# OpenBook_Schematic_v38.net
KiCad netlist of a schematic drawn in EAGLE
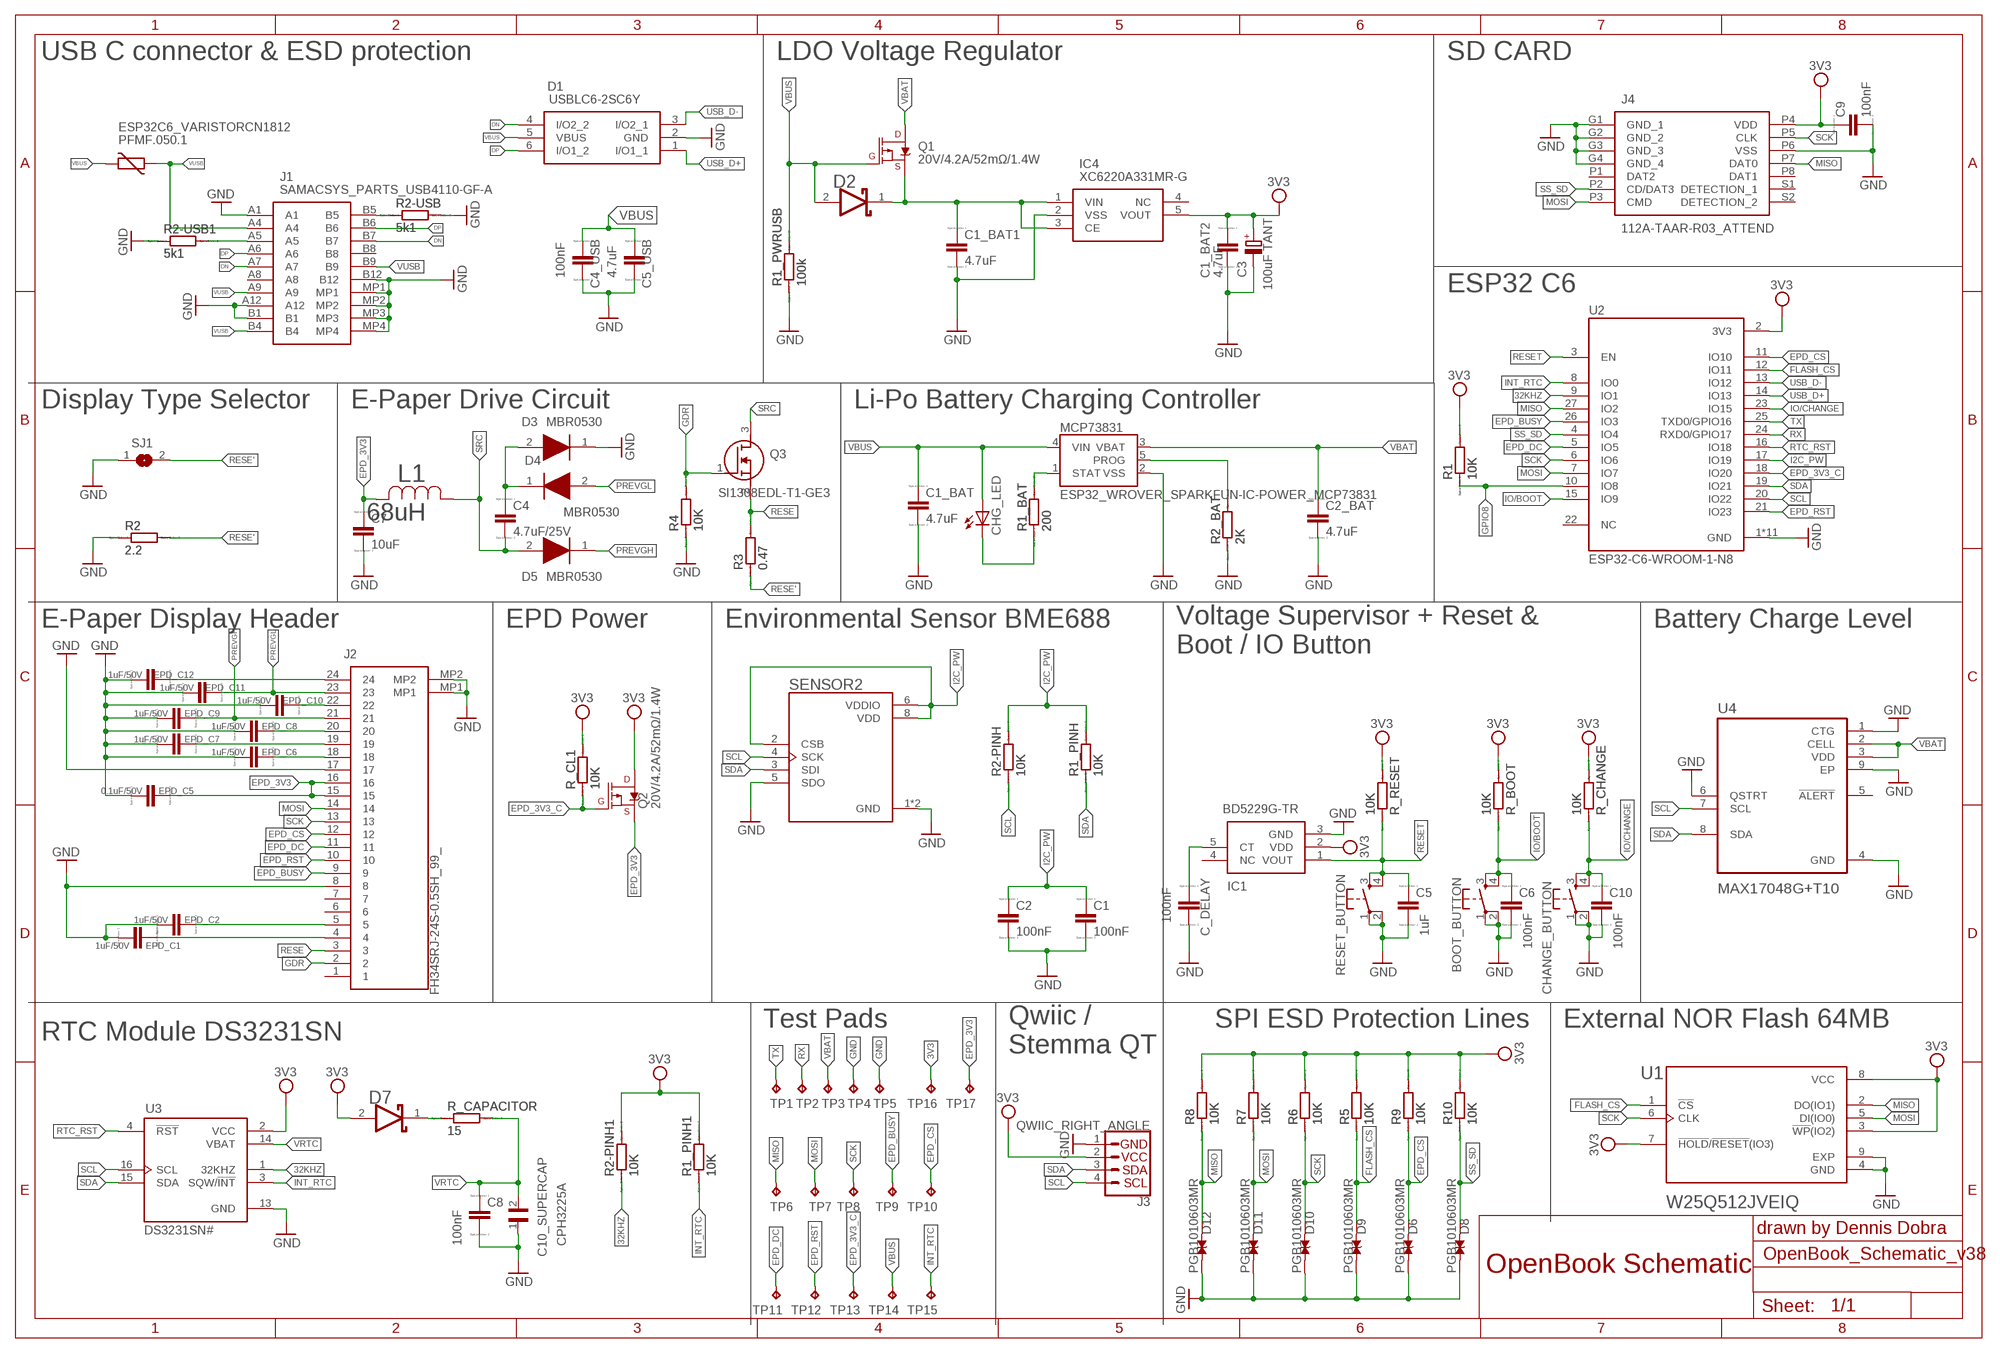
[diagram p0: schematic, sheet 1]

(export (version "E")
  (design (tool "Eeschema 10.0.6"))
  (components
    (comp (ref "BOOT_BUTTON")
      (value "BUTTON_CUSYOMV1")
      (footprint "eagle-import:MYBUTTON")
      (libsource (lib "eagle-import") (part "BUTTON_CUSYOMV1"))
    )
    (comp (ref "C1")
      (value "100nF")
      (footprint "eagle-import:EAGLE-LTSPICE_C0402")
      (libsource (lib "eagle-import") (part "EAGLE-LTSPICE_CC0402"))
    )
    (comp (ref "C1_BAT")
      (value "4.7uF")
      (footprint "eagle-import:EAGLE-LTSPICE_C0402")
      (libsource (lib "eagle-import") (part "EAGLE-LTSPICE_CC0402"))
    )
    (comp (ref "C1_BAT1")
      (value "4.7uF")
      (footprint "eagle-import:EAGLE-LTSPICE_C0402")
      (libsource (lib "eagle-import") (part "EAGLE-LTSPICE_CC0402"))
    )
    (comp (ref "C1_BAT2")
      (value "4.7uF")
      (footprint "eagle-import:EAGLE-LTSPICE_C0402")
      (libsource (lib "eagle-import") (part "EAGLE-LTSPICE_CC0402"))
    )
    (comp (ref "C2")
      (value "100nF")
      (footprint "eagle-import:EAGLE-LTSPICE_C0402")
      (libsource (lib "eagle-import") (part "EAGLE-LTSPICE_CC0402"))
    )
    (comp (ref "C2_BAT")
      (value "4.7uF")
      (footprint "eagle-import:EAGLE-LTSPICE_C0402")
      (libsource (lib "eagle-import") (part "EAGLE-LTSPICE_CC0402"))
    )
    (comp (ref "C3")
      (value "100uF TANT")
      (footprint "eagle-import:RCL_CT3528")
      (libsource (lib "eagle-import") (part "RCL_CPOL-EUCT3528"))
    )
    (comp (ref "C4")
      (value "4.7uF/25V")
      (footprint "eagle-import:EAGLE-LTSPICE_C0402")
      (libsource (lib "eagle-import") (part "EAGLE-LTSPICE_CC0402"))
    )
    (comp (ref "C4_USB")
      (value "100nF")
      (footprint "eagle-import:EAGLE-LTSPICE_C0402")
      (libsource (lib "eagle-import") (part "EAGLE-LTSPICE_CC0402"))
    )
    (comp (ref "C5")
      (value "1uF")
      (footprint "eagle-import:EAGLE-LTSPICE_C0402")
      (libsource (lib "eagle-import") (part "EAGLE-LTSPICE_CC0402"))
    )
    (comp (ref "C5_USB")
      (value "4.7uF")
      (footprint "eagle-import:EAGLE-LTSPICE_C0402")
      (libsource (lib "eagle-import") (part "EAGLE-LTSPICE_CC0402"))
    )
    (comp (ref "C6")
      (value "100nF")
      (footprint "eagle-import:EAGLE-LTSPICE_C0402")
      (libsource (lib "eagle-import") (part "EAGLE-LTSPICE_CC0402"))
    )
    (comp (ref "C7")
      (value "10uF")
      (footprint "eagle-import:EAGLE-LTSPICE_C0402")
      (libsource (lib "eagle-import") (part "EAGLE-LTSPICE_CC0402"))
    )
    (comp (ref "C8")
      (value "100nF")
      (footprint "eagle-import:EAGLE-LTSPICE_C0402")
      (libsource (lib "eagle-import") (part "EAGLE-LTSPICE_CC0402"))
    )
    (comp (ref "C9")
      (value "100nF")
      (footprint "eagle-import:EAGLE-LTSPICE_C0402")
      (libsource (lib "eagle-import") (part "EAGLE-LTSPICE_CC0402"))
    )
    (comp (ref "C10")
      (value "100nF")
      (footprint "eagle-import:EAGLE-LTSPICE_C0402")
      (libsource (lib "eagle-import") (part "EAGLE-LTSPICE_CC0402"))
    )
    (comp (ref "C10_SUPERCAP")
      (value "CPH3225A")
      (footprint "eagle-import:CAPCP3225X100N")
      (fields (field (name "MF") "Seiko Instruments"))
      (libsource (lib "eagle-import") (part "CPH3225A"))
    )
    (comp (ref "CHANGE_BUTTON")
      (value "BUTTON_CUSYOMV1")
      (footprint "eagle-import:MYBUTTON")
      (libsource (lib "eagle-import") (part "BUTTON_CUSYOMV1"))
    )
    (comp (ref "CHG_LED")
      (value "ADAFRUIT_LEDCHIP-LED0603")
      (footprint "eagle-import:ADAFRUIT_CHIP-LED0603")
      (libsource (lib "eagle-import") (part "ADAFRUIT_LEDCHIP-LED0603"))
    )
    (comp (ref "C_DELAY")
      (value "100nF")
      (footprint "eagle-import:EAGLE-LTSPICE_C0402")
      (libsource (lib "eagle-import") (part "EAGLE-LTSPICE_CC0402"))
    )
    (comp (ref "D1")
      (value "USBLC6-2SC6Y")
      (footprint "eagle-import:SOT95P280X145-6N")
      (fields (field (name "MF") "STMicroelectronics"))
      (libsource (lib "eagle-import") (part "USBLC6-2SC6Y"))
    )
    (comp (ref "D2")
      (value "ESP32_WROVER_AVX---SD0805S020S1R0_AVX_SD0805S020S1R0_0_0AVX_SD0805S020S1R0_0_0")
      (footprint "eagle-import:ESP32_WROVER_AVX---SD0805S020S1R0_AVX_SD0805S020S1R0_0")
      (fields
        (field (name "DIGIKEY_PART_NUMBER") "478-7800-1-ND")
        (field (name "MF") "AVX")
        (field (name "MOUSER_PART_NUMBER") "581-SD0805S020S1R0")
      )
      (libsource (lib "eagle-import") (part "ESP32_WROVER_AVX---SD0805S020S1R0_AVX_SD0805S020S1R0_0_0AVX_SD0805S020S1R0_0_0"))
    )
    (comp (ref "D3")
      (value "MBR0530")
      (footprint "eagle-import:SOD3716X135N")
      (fields (field (name "MF") "ON Semiconductor"))
      (libsource (lib "eagle-import") (part "MBR0530"))
    )
    (comp (ref "D4")
      (value "MBR0530")
      (footprint "eagle-import:SOD3716X135N")
      (fields (field (name "MF") "ON Semiconductor"))
      (libsource (lib "eagle-import") (part "MBR0530"))
    )
    (comp (ref "D5")
      (value "MBR0530")
      (footprint "eagle-import:SOD3716X135N")
      (fields (field (name "MF") "ON Semiconductor"))
      (libsource (lib "eagle-import") (part "MBR0530"))
    )
    (comp (ref "D6")
      (value "PGB1010603MR")
      (footprint "eagle-import:DIOC1608X36N")
      (fields (field (name "MF") "Littelfuse Inc."))
      (libsource (lib "eagle-import") (part "PGB1010603MR"))
    )
    (comp (ref "D7")
      (value "ESP32_WROVER_AVX---SD0805S020S1R0_AVX_SD0805S020S1R0_0_0AVX_SD0805S020S1R0_0_0")
      (footprint "eagle-import:ESP32_WROVER_AVX---SD0805S020S1R0_AVX_SD0805S020S1R0_0")
      (fields
        (field (name "DIGIKEY_PART_NUMBER") "478-7800-1-ND")
        (field (name "MF") "AVX")
        (field (name "MOUSER_PART_NUMBER") "581-SD0805S020S1R0")
      )
      (libsource (lib "eagle-import") (part "ESP32_WROVER_AVX---SD0805S020S1R0_AVX_SD0805S020S1R0_0_0AVX_SD0805S020S1R0_0_0"))
    )
    (comp (ref "D8")
      (value "PGB1010603MR")
      (footprint "eagle-import:DIOC1608X36N")
      (fields (field (name "MF") "Littelfuse Inc."))
      (libsource (lib "eagle-import") (part "PGB1010603MR"))
    )
    (comp (ref "D9")
      (value "PGB1010603MR")
      (footprint "eagle-import:DIOC1608X36N")
      (fields (field (name "MF") "Littelfuse Inc."))
      (libsource (lib "eagle-import") (part "PGB1010603MR"))
    )
    (comp (ref "D10")
      (value "PGB1010603MR")
      (footprint "eagle-import:DIOC1608X36N")
      (fields (field (name "MF") "Littelfuse Inc."))
      (libsource (lib "eagle-import") (part "PGB1010603MR"))
    )
    (comp (ref "D11")
      (value "PGB1010603MR")
      (footprint "eagle-import:DIOC1608X36N")
      (fields (field (name "MF") "Littelfuse Inc."))
      (libsource (lib "eagle-import") (part "PGB1010603MR"))
    )
    (comp (ref "D12")
      (value "PGB1010603MR")
      (footprint "eagle-import:DIOC1608X36N")
      (fields (field (name "MF") "Littelfuse Inc."))
      (libsource (lib "eagle-import") (part "PGB1010603MR"))
    )
    (comp (ref "EPD_C1")
      (value "1uF/50V")
      (footprint "eagle-import:EAGLE-LTSPICE_C0402")
      (libsource (lib "eagle-import") (part "EAGLE-LTSPICE_CC0402"))
    )
    (comp (ref "EPD_C2")
      (value "1uF/50V")
      (footprint "eagle-import:EAGLE-LTSPICE_C0402")
      (libsource (lib "eagle-import") (part "EAGLE-LTSPICE_CC0402"))
    )
    (comp (ref "EPD_C5")
      (value "0.1uF/50V")
      (footprint "eagle-import:EAGLE-LTSPICE_C0402")
      (libsource (lib "eagle-import") (part "EAGLE-LTSPICE_CC0402"))
    )
    (comp (ref "EPD_C6")
      (value "1uF/50V")
      (footprint "eagle-import:EAGLE-LTSPICE_C0402")
      (libsource (lib "eagle-import") (part "EAGLE-LTSPICE_CC0402"))
    )
    (comp (ref "EPD_C7")
      (value "1uF/50V")
      (footprint "eagle-import:EAGLE-LTSPICE_C0402")
      (libsource (lib "eagle-import") (part "EAGLE-LTSPICE_CC0402"))
    )
    (comp (ref "EPD_C8")
      (value "1uF/50V")
      (footprint "eagle-import:EAGLE-LTSPICE_C0402")
      (libsource (lib "eagle-import") (part "EAGLE-LTSPICE_CC0402"))
    )
    (comp (ref "EPD_C9")
      (value "1uF/50V")
      (footprint "eagle-import:EAGLE-LTSPICE_C0402")
      (libsource (lib "eagle-import") (part "EAGLE-LTSPICE_CC0402"))
    )
    (comp (ref "EPD_C10")
      (value "1uF/50V")
      (footprint "eagle-import:EAGLE-LTSPICE_C0402")
      (libsource (lib "eagle-import") (part "EAGLE-LTSPICE_CC0402"))
    )
    (comp (ref "EPD_C11")
      (value "1uF/50V")
      (footprint "eagle-import:EAGLE-LTSPICE_C0402")
      (libsource (lib "eagle-import") (part "EAGLE-LTSPICE_CC0402"))
    )
    (comp (ref "EPD_C12")
      (value "1uF/50V")
      (footprint "eagle-import:EAGLE-LTSPICE_C0402")
      (libsource (lib "eagle-import") (part "EAGLE-LTSPICE_CC0402"))
    )
    (comp (ref "IC1")
      (value "BD5229G-TR")
      (footprint "eagle-import:SOT95P280X125-5N")
      (fields (field (name "MOUSER_PART_NUMBER") "755-BD5229G-TR"))
      (libsource (lib "eagle-import") (part "BD5229G-TR"))
    )
    (comp (ref "IC4")
      (value "XC6220A331MR-G")
      (footprint "eagle-import:SOT95P280X120-5N")
      (fields (field (name "MOUSER_PART_NUMBER") "865-XC6220A331MR-G"))
      (libsource (lib "eagle-import") (part "XC6220A331MR-G"))
    )
    (comp (ref "J1")
      (value "SAMACSYS_PARTS_USB4110-GF-A")
      (footprint "eagle-import:SAMACSYS_PARTS_USB4110GFA")
      (fields
        (field (name "MANUFACTURER_PART_NUMBER") "USB4110-GF-A")
        (field (name "MOUSER_PART_NUMBER") "640-USB4110-GF-A")
      )
      (libsource (lib "eagle-import") (part "SAMACSYS_PARTS_USB4110-GF-A"))
    )
    (comp (ref "J2")
      (value "FH34SRJ-24S-0.5SH_99_")
      (footprint "eagle-import:FH34SRJ24S05SH99")
      (fields
        (field (name "MANUFACTURER_PART_NUMBER") "FH34SRJ-24S-0.5SH(99)")
        (field (name "MOUSER_PART_NUMBER") "798-FH34SRJ24S05SH99")
      )
      (libsource (lib "eagle-import") (part "FH34SRJ-24S-0.5SH_99_"))
    )
    (comp (ref "J3")
      (value "QWIIC_RIGHT_ANGLE")
      (footprint "eagle-import:JST04_1MM_RA")
      (libsource (lib "eagle-import") (part "QWIIC_CONNECTORJS-1MM"))
    )
    (comp (ref "J4")
      (value "112A-TAAR-R03_ATTEND")
      (footprint "eagle-import:112ATAARR03ATTEND")
      (fields (field (name "MANUFACTURER_PART_NUMBER") "112A-TAAR-R03 ATTEND"))
      (libsource (lib "eagle-import") (part "112A-TAAR-R03_ATTEND"))
    )
    (comp (ref "L1")
      (value "68uH")
      (footprint "eagle-import:IND_4828-WE-TPC_WRE")
      (fields
        (field (name "MANUFACTURER_PART_NUMBER") "744043680")
        (field (name "COPYRIGHT") "Copyright (C) 2024 Ultra Librarian. All rights reserved.")
      )
      (libsource (lib "eagle-import") (part "744043680IND_4828-WE-TPC_WRE"))
    )
    (comp (ref "MCP73831")
      (value "ESP32_WROVER_SPARKFUN-IC-POWER_MCP73831")
      (footprint "eagle-import:ESP32_WROVER_SPARKFUN-IC-POWER_SOT23-5")
      (libsource (lib "eagle-import") (part "ESP32_WROVER_SPARKFUN-IC-POWER_MCP73831"))
    )
    (comp (ref "PFMF.050.1")
      (value "ESP32C6_VARISTORCN1812")
      (footprint "eagle-import:ESP32C6_VARISTOR_CT_CN1812")
      (libsource (lib "eagle-import") (part "ESP32C6_VARISTORCN1812"))
    )
    (comp (ref "Q1")
      (value "20V/4.2A/52mΩ/1.4W")
      (footprint "eagle-import:ESP32_WROVER_SPARKFUN-DISCRETESEMI_SOT23-3")
      (libsource (lib "eagle-import") (part "ESP32_WROVER_SPARKFUN-DISCRETESEMI_MOSFET_PCH-DMG2305UX-7"))
    )
    (comp (ref "Q2")
      (value "20V/4.2A/52mΩ/1.4W")
      (footprint "eagle-import:ESP32_WROVER_SPARKFUN-DISCRETESEMI_SOT23-3")
      (libsource (lib "eagle-import") (part "ESP32_WROVER_SPARKFUN-DISCRETESEMI_MOSFET_PCH-DMG2305UX-7"))
    )
    (comp (ref "Q3")
      (value "SI1308EDL-T1-GE3")
      (footprint "eagle-import:SOT65P210X110-3N")
      (fields (field (name "MF") "Vishay Siliconix"))
      (libsource (lib "eagle-import") (part "SI1308EDL-T1-GE3"))
    )
    (comp (ref "R1")
      (value "10K")
      (footprint "eagle-import:ESP32_WROVER_EAGLE-LTSPICE_R0402")
      (libsource (lib "eagle-import") (part "ESP32_WROVER_EAGLE-LTSPICE_RR0402"))
    )
    (comp (ref "R1_BAT")
      (value "200")
      (footprint "eagle-import:ESP32_WROVER_EAGLE-LTSPICE_R0402")
      (libsource (lib "eagle-import") (part "ESP32_WROVER_EAGLE-LTSPICE_RR0402"))
    )
    (comp (ref "R1_PINH")
      (value "10K")
      (footprint "eagle-import:ESP32_WROVER_EAGLE-LTSPICE_R0402")
      (libsource (lib "eagle-import") (part "ESP32_WROVER_EAGLE-LTSPICE_RR0402"))
    )
    (comp (ref "R1_PINH1")
      (value "10K")
      (footprint "eagle-import:ESP32_WROVER_EAGLE-LTSPICE_R0402")
      (libsource (lib "eagle-import") (part "ESP32_WROVER_EAGLE-LTSPICE_RR0402"))
    )
    (comp (ref "R1_PWRUSB")
      (value "100k")
      (footprint "eagle-import:ESP32_WROVER_EAGLE-LTSPICE_R0402")
      (libsource (lib "eagle-import") (part "ESP32_WROVER_EAGLE-LTSPICE_RR0402"))
    )
    (comp (ref "R2")
      (value "2.2")
      (footprint "eagle-import:ESP32_WROVER_EAGLE-LTSPICE_R0402")
      (libsource (lib "eagle-import") (part "ESP32_WROVER_EAGLE-LTSPICE_RR0402"))
    )
    (comp (ref "R2-PINH")
      (value "10K")
      (footprint "eagle-import:ESP32_WROVER_EAGLE-LTSPICE_R0402")
      (libsource (lib "eagle-import") (part "ESP32_WROVER_EAGLE-LTSPICE_RR0402"))
    )
    (comp (ref "R2-PINH1")
      (value "10K")
      (footprint "eagle-import:ESP32_WROVER_EAGLE-LTSPICE_R0402")
      (libsource (lib "eagle-import") (part "ESP32_WROVER_EAGLE-LTSPICE_RR0402"))
    )
    (comp (ref "R2-USB")
      (value "5k1")
      (footprint "eagle-import:ESP32_WROVER_EAGLE-LTSPICE_R0402")
      (libsource (lib "eagle-import") (part "ESP32_WROVER_EAGLE-LTSPICE_RR0402"))
    )
    (comp (ref "R2-USB1")
      (value "5k1")
      (footprint "eagle-import:ESP32_WROVER_EAGLE-LTSPICE_R0402")
      (libsource (lib "eagle-import") (part "ESP32_WROVER_EAGLE-LTSPICE_RR0402"))
    )
    (comp (ref "R2_BAT")
      (value "2K")
      (footprint "eagle-import:ESP32_WROVER_EAGLE-LTSPICE_R0402")
      (libsource (lib "eagle-import") (part "ESP32_WROVER_EAGLE-LTSPICE_RR0402"))
    )
    (comp (ref "R3")
      (value "0.47")
      (footprint "eagle-import:ESP32_WROVER_EAGLE-LTSPICE_R0402")
      (libsource (lib "eagle-import") (part "ESP32_WROVER_EAGLE-LTSPICE_RR0402"))
    )
    (comp (ref "R4")
      (value "10K")
      (footprint "eagle-import:ESP32_WROVER_EAGLE-LTSPICE_R0402")
      (libsource (lib "eagle-import") (part "ESP32_WROVER_EAGLE-LTSPICE_RR0402"))
    )
    (comp (ref "R5")
      (value "10K")
      (footprint "eagle-import:ESP32_WROVER_EAGLE-LTSPICE_R0402")
      (libsource (lib "eagle-import") (part "ESP32_WROVER_EAGLE-LTSPICE_RR0402"))
    )
    (comp (ref "R6")
      (value "10K")
      (footprint "eagle-import:ESP32_WROVER_EAGLE-LTSPICE_R0402")
      (libsource (lib "eagle-import") (part "ESP32_WROVER_EAGLE-LTSPICE_RR0402"))
    )
    (comp (ref "R7")
      (value "10K")
      (footprint "eagle-import:ESP32_WROVER_EAGLE-LTSPICE_R0402")
      (libsource (lib "eagle-import") (part "ESP32_WROVER_EAGLE-LTSPICE_RR0402"))
    )
    (comp (ref "R8")
      (value "10K")
      (footprint "eagle-import:ESP32_WROVER_EAGLE-LTSPICE_R0402")
      (libsource (lib "eagle-import") (part "ESP32_WROVER_EAGLE-LTSPICE_RR0402"))
    )
    (comp (ref "R9")
      (value "10K")
      (footprint "eagle-import:ESP32_WROVER_EAGLE-LTSPICE_R0402")
      (libsource (lib "eagle-import") (part "ESP32_WROVER_EAGLE-LTSPICE_RR0402"))
    )
    (comp (ref "R10")
      (value "10K")
      (footprint "eagle-import:ESP32_WROVER_EAGLE-LTSPICE_R0402")
      (libsource (lib "eagle-import") (part "ESP32_WROVER_EAGLE-LTSPICE_RR0402"))
    )
    (comp (ref "RESET_BUTTON")
      (value "BUTTON_CUSYOMV1")
      (footprint "eagle-import:MYBUTTON")
      (libsource (lib "eagle-import") (part "BUTTON_CUSYOMV1"))
    )
    (comp (ref "R_BOOT")
      (value "10K")
      (footprint "eagle-import:ESP32_WROVER_EAGLE-LTSPICE_R0402")
      (libsource (lib "eagle-import") (part "ESP32_WROVER_EAGLE-LTSPICE_RR0402"))
    )
    (comp (ref "R_CAPACITOR")
      (value "15")
      (footprint "eagle-import:ESP32_WROVER_EAGLE-LTSPICE_R0402")
      (libsource (lib "eagle-import") (part "ESP32_WROVER_EAGLE-LTSPICE_RR0402"))
    )
    (comp (ref "R_CHANGE")
      (value "10K")
      (footprint "eagle-import:ESP32_WROVER_EAGLE-LTSPICE_R0402")
      (libsource (lib "eagle-import") (part "ESP32_WROVER_EAGLE-LTSPICE_RR0402"))
    )
    (comp (ref "R_CL1")
      (value "10K")
      (footprint "eagle-import:ESP32_WROVER_EAGLE-LTSPICE_R0402")
      (libsource (lib "eagle-import") (part "ESP32_WROVER_EAGLE-LTSPICE_RR0402"))
    )
    (comp (ref "R_RESET")
      (value "10K")
      (footprint "eagle-import:ESP32_WROVER_EAGLE-LTSPICE_R0402")
      (libsource (lib "eagle-import") (part "ESP32_WROVER_EAGLE-LTSPICE_RR0402"))
    )
    (comp (ref "SENSOR2")
      (value "ESP32_WROVER_BME680_BME680")
      (footprint "eagle-import:ESP32_WROVER_BME680_PSON80P300X300X100-8N")
      (fields (field (name "MF") "Bosch Sensortec") (field (name "MP") "BME680"))
      (libsource (lib "eagle-import") (part "ESP32_WROVER_BME680_BME680"))
    )
    (comp (ref "SJ1") (value "SJ") (footprint "eagle-import:SJ") (libsource (lib "eagle-import") (part "SJ")))
    (comp (ref "TP1")
      (value "TPTP20R")
      (footprint "eagle-import:TP20R")
      (libsource (lib "eagle-import") (part "TPTP20R"))
    )
    (comp (ref "TP2")
      (value "TPTP20R")
      (footprint "eagle-import:TP20R")
      (libsource (lib "eagle-import") (part "TPTP20R"))
    )
    (comp (ref "TP3")
      (value "TPTP20R")
      (footprint "eagle-import:TP20R")
      (libsource (lib "eagle-import") (part "TPTP20R"))
    )
    (comp (ref "TP4")
      (value "TPTP20R")
      (footprint "eagle-import:TP20R")
      (libsource (lib "eagle-import") (part "TPTP20R"))
    )
    (comp (ref "TP5")
      (value "TPTP20R")
      (footprint "eagle-import:TP20R")
      (libsource (lib "eagle-import") (part "TPTP20R"))
    )
    (comp (ref "TP6")
      (value "TPTP20R")
      (footprint "eagle-import:TP20R")
      (libsource (lib "eagle-import") (part "TPTP20R"))
    )
    (comp (ref "TP7")
      (value "TPTP20R")
      (footprint "eagle-import:TP20R")
      (libsource (lib "eagle-import") (part "TPTP20R"))
    )
    (comp (ref "TP8")
      (value "TPTP20R")
      (footprint "eagle-import:TP20R")
      (libsource (lib "eagle-import") (part "TPTP20R"))
    )
    (comp (ref "TP9")
      (value "TPTP20R")
      (footprint "eagle-import:TP20R")
      (libsource (lib "eagle-import") (part "TPTP20R"))
    )
    (comp (ref "TP10")
      (value "TPTP20R")
      (footprint "eagle-import:TP20R")
      (libsource (lib "eagle-import") (part "TPTP20R"))
    )
    (comp (ref "TP11")
      (value "TPTP20R")
      (footprint "eagle-import:TP20R")
      (libsource (lib "eagle-import") (part "TPTP20R"))
    )
    (comp (ref "TP12")
      (value "TPTP20R")
      (footprint "eagle-import:TP20R")
      (libsource (lib "eagle-import") (part "TPTP20R"))
    )
    (comp (ref "TP13")
      (value "TPTP20R")
      (footprint "eagle-import:TP20R")
      (libsource (lib "eagle-import") (part "TPTP20R"))
    )
    (comp (ref "TP14")
      (value "TPTP20R")
      (footprint "eagle-import:TP20R")
      (libsource (lib "eagle-import") (part "TPTP20R"))
    )
    (comp (ref "TP15")
      (value "TPTP20R")
      (footprint "eagle-import:TP20R")
      (libsource (lib "eagle-import") (part "TPTP20R"))
    )
    (comp (ref "TP16")
      (value "TPTP20R")
      (footprint "eagle-import:TP20R")
      (libsource (lib "eagle-import") (part "TPTP20R"))
    )
    (comp (ref "TP17")
      (value "TPTP20R")
      (footprint "eagle-import:TP20R")
      (libsource (lib "eagle-import") (part "TPTP20R"))
    )
    (comp (ref "U1")
      (value "W25Q512JVEIQ")
      (footprint "eagle-import:SON127P600X800X80-9N")
      (fields (field (name "MF") "Winbond Electronics"))
      (libsource (lib "eagle-import") (part "W25Q512JVEIQ"))
    )
    (comp (ref "U2")
      (value "ESP32-C6-WROOM-1-N8")
      (footprint "eagle-import:XCVR_ESP32-C6-WROOM-1-N8")
      (fields (field (name "MF") "Espressif Systems"))
      (libsource (lib "eagle-import") (part "ESP32-C6-WROOM-1-N8"))
    )
    (comp (ref "U3")
      (value "DS3231SN#")
      (footprint "eagle-import:SOIC127P1032X265-16N")
      (fields (field (name "MF") "Analog Devices"))
      (libsource (lib "eagle-import") (part "DS3231SN#"))
    )
    (comp (ref "U4")
      (value "MAX17048G+T10")
      (footprint "eagle-import:SON50P200X200X80-9N")
      (fields (field (name "MF") "Analog Devices"))
      (libsource (lib "eagle-import") (part "MAX17048G+T10"))
    )
  )
  (nets
    (net (code "1") (name "3V3") (class "Default")
      (node (ref "C1_BAT2") (pin "1") (pinfunction "1_1") (pintype "passive"))
      (node (ref "C3") (pin "+") (pinfunction "+_+") (pintype "passive"))
      (node (ref "C9") (pin "1") (pinfunction "1_1") (pintype "passive"))
      (node (ref "D7") (pin "2") (pinfunction "ANODE_2") (pintype "bidirectional"))
      (node (ref "IC1") (pin "2") (pinfunction "VDD_2") (pintype "bidirectional"))
      (node (ref "IC4") (pin "5") (pinfunction "VOUT_5") (pintype "bidirectional"))
      (node (ref "J3") (pin "2") (pinfunction "2_2") (pintype "power_in"))
      (node (ref "J4") (pin "P4") (pinfunction "VDD_P4") (pintype "bidirectional"))
      (node (ref "Q2") (pin "3") (pinfunction "D_3") (pintype "bidirectional"))
      (node (ref "R1") (pin "2") (pinfunction "2_2") (pintype "passive"))
      (node (ref "R10") (pin "2") (pinfunction "2_2") (pintype "passive"))
      (node (ref "R1_PINH1") (pin "2") (pinfunction "2_2") (pintype "passive"))
      (node (ref "R2-PINH1") (pin "2") (pinfunction "2_2") (pintype "passive"))
      (node (ref "R5") (pin "2") (pinfunction "2_2") (pintype "passive"))
      (node (ref "R6") (pin "2") (pinfunction "2_2") (pintype "passive"))
      (node (ref "R7") (pin "2") (pinfunction "2_2") (pintype "passive"))
      (node (ref "R8") (pin "2") (pinfunction "2_2") (pintype "passive"))
      (node (ref "R9") (pin "2") (pinfunction "2_2") (pintype "passive"))
      (node (ref "R_BOOT") (pin "2") (pinfunction "2_2") (pintype "passive"))
      (node (ref "R_CHANGE") (pin "2") (pinfunction "2_2") (pintype "passive"))
      (node (ref "R_CL1") (pin "2") (pinfunction "2_2") (pintype "passive"))
      (node (ref "R_RESET") (pin "2") (pinfunction "2_2") (pintype "passive"))
      (node (ref "TP16") (pin "TP") (pinfunction "TP_TP") (pintype "input"))
      (node (ref "U1") (pin "3") (pinfunction "~{WP}(IO2)_3") (pintype "bidirectional"))
      (node (ref "U1") (pin "7") (pinfunction "~{HOLD}/~{RESET}(IO3)_7") (pintype "bidirectional"))
      (node (ref "U1") (pin "8") (pinfunction "VCC_8") (pintype "power_in"))
      (node (ref "U2") (pin "2") (pinfunction "3V3_2") (pintype "power_in"))
      (node (ref "U3") (pin "2") (pinfunction "VCC_2") (pintype "power_in"))
    )
    (net (code "2") (name "32KHZ") (class "Default")
      (node (ref "R2-PINH1") (pin "1") (pinfunction "1_1") (pintype "passive"))
      (node (ref "U2") (pin "9") (pinfunction "IO1_9") (pintype "bidirectional"))
      (node (ref "U3") (pin "1") (pinfunction "32KHZ_1") (pintype "output"))
    )
    (net (code "3") (name "DN") (class "Default")
      (node (ref "D1") (pin "4") (pinfunction "I/O2_2_4") (pintype "bidirectional"))
      (node (ref "J1") (pin "A7") (pinfunction "A7_A7") (pintype "bidirectional"))
      (node (ref "J1") (pin "B7") (pinfunction "B7_B7") (pintype "bidirectional"))
    )
    (net (code "4") (name "DP") (class "Default")
      (node (ref "D1") (pin "6") (pinfunction "I/O1_2_6") (pintype "bidirectional"))
      (node (ref "J1") (pin "A6") (pinfunction "A6_A6") (pintype "bidirectional"))
      (node (ref "J1") (pin "B6") (pinfunction "B6_B6") (pintype "bidirectional"))
    )
    (net (code "5") (name "EPD_3V3") (class "Default")
      (node (ref "C7") (pin "1") (pinfunction "1_1") (pintype "passive"))
      (node (ref "EPD_C5") (pin "2") (pinfunction "2_2") (pintype "passive"))
      (node (ref "J2") (pin "15") (pinfunction "15_15") (pintype "bidirectional"))
      (node (ref "J2") (pin "16") (pinfunction "16_16") (pintype "bidirectional"))
      (node (ref "L1") (pin "2") (pinfunction "2_2") (pintype "passive"))
      (node (ref "Q2") (pin "2") (pinfunction "S_2") (pintype "bidirectional"))
      (node (ref "TP17") (pin "TP") (pinfunction "TP_TP") (pintype "input"))
    )
    (net (code "6") (name "EPD_3V3_C") (class "Default")
      (node (ref "Q2") (pin "1") (pinfunction "G_1") (pintype "bidirectional"))
      (node (ref "R_CL1") (pin "1") (pinfunction "1_1") (pintype "passive"))
      (node (ref "TP13") (pin "TP") (pinfunction "TP_TP") (pintype "input"))
      (node (ref "U2") (pin "18") (pinfunction "IO20_18") (pintype "bidirectional"))
    )
    (net (code "7") (name "EPD_BUSY") (class "Default")
      (node (ref "J2") (pin "9") (pinfunction "9_9") (pintype "bidirectional"))
      (node (ref "TP9") (pin "TP") (pinfunction "TP_TP") (pintype "input"))
      (node (ref "U2") (pin "26") (pinfunction "IO3_26") (pintype "bidirectional"))
    )
    (net (code "8") (name "EPD_CS") (class "Default")
      (node (ref "D6") (pin "2") (pinfunction "2_2") (pintype "passive"))
      (node (ref "J2") (pin "12") (pinfunction "12_12") (pintype "bidirectional"))
      (node (ref "R9") (pin "1") (pinfunction "1_1") (pintype "passive"))
      (node (ref "TP10") (pin "TP") (pinfunction "TP_TP") (pintype "input"))
      (node (ref "U2") (pin "11") (pinfunction "IO10_11") (pintype "bidirectional"))
    )
    (net (code "9") (name "EPD_DC") (class "Default")
      (node (ref "J2") (pin "11") (pinfunction "11_11") (pintype "bidirectional"))
      (node (ref "TP11") (pin "TP") (pinfunction "TP_TP") (pintype "input"))
      (node (ref "U2") (pin "5") (pinfunction "IO5_5") (pintype "bidirectional"))
    )
    (net (code "10") (name "EPD_RST") (class "Default")
      (node (ref "J2") (pin "10") (pinfunction "10_10") (pintype "bidirectional"))
      (node (ref "TP12") (pin "TP") (pinfunction "TP_TP") (pintype "input"))
      (node (ref "U2") (pin "21") (pinfunction "IO23_21") (pintype "bidirectional"))
    )
    (net (code "11") (name "FLASH_CS") (class "Default")
      (node (ref "D9") (pin "2") (pinfunction "2_2") (pintype "passive"))
      (node (ref "R5") (pin "1") (pinfunction "1_1") (pintype "passive"))
      (node (ref "U1") (pin "1") (pinfunction "~{CS}_1") (pintype "input"))
      (node (ref "U2") (pin "12") (pinfunction "IO11_12") (pintype "bidirectional"))
    )
    (net (code "12") (name "GDR") (class "Default")
      (node (ref "J2") (pin "2") (pinfunction "2_2") (pintype "bidirectional"))
      (node (ref "Q3") (pin "1") (pinfunction "G_1") (pintype "bidirectional"))
      (node (ref "R4") (pin "2") (pinfunction "2_2") (pintype "passive"))
    )
    (net (code "13") (name "GND") (class "Default")
      (node (ref "BOOT_BUTTON") (pin "1") (pinfunction "1_1") (pintype "passive"))
      (node (ref "BOOT_BUTTON") (pin "2") (pinfunction "2_2") (pintype "passive"))
      (node (ref "C1") (pin "2") (pinfunction "2_2") (pintype "passive"))
      (node (ref "C10") (pin "2") (pinfunction "2_2") (pintype "passive"))
      (node (ref "C10_SUPERCAP") (pin "1") (pinfunction "1_1") (pintype "passive"))
      (node (ref "C1_BAT") (pin "2") (pinfunction "2_2") (pintype "passive"))
      (node (ref "C1_BAT1") (pin "2") (pinfunction "2_2") (pintype "passive"))
      (node (ref "C1_BAT2") (pin "2") (pinfunction "2_2") (pintype "passive"))
      (node (ref "C2") (pin "2") (pinfunction "2_2") (pintype "passive"))
      (node (ref "C2_BAT") (pin "2") (pinfunction "2_2") (pintype "passive"))
      (node (ref "C3") (pin "-") (pinfunction "-_-") (pintype "passive"))
      (node (ref "C4_USB") (pin "2") (pinfunction "2_2") (pintype "passive"))
      (node (ref "C5") (pin "2") (pinfunction "2_2") (pintype "passive"))
      (node (ref "C5_USB") (pin "2") (pinfunction "2_2") (pintype "passive"))
      (node (ref "C6") (pin "2") (pinfunction "2_2") (pintype "passive"))
      (node (ref "C7") (pin "2") (pinfunction "2_2") (pintype "passive"))
      (node (ref "C8") (pin "2") (pinfunction "2_2") (pintype "passive"))
      (node (ref "C9") (pin "2") (pinfunction "2_2") (pintype "passive"))
      (node (ref "CHANGE_BUTTON") (pin "1") (pinfunction "1_1") (pintype "passive"))
      (node (ref "CHANGE_BUTTON") (pin "2") (pinfunction "2_2") (pintype "passive"))
      (node (ref "C_DELAY") (pin "2") (pinfunction "2_2") (pintype "passive"))
      (node (ref "D1") (pin "2") (pinfunction "GND_2") (pintype "bidirectional"))
      (node (ref "D10") (pin "1") (pinfunction "1_1") (pintype "passive"))
      (node (ref "D11") (pin "1") (pinfunction "1_1") (pintype "passive"))
      (node (ref "D12") (pin "1") (pinfunction "1_1") (pintype "passive"))
      (node (ref "D3") (pin "1") (pinfunction "K_1") (pintype "bidirectional"))
      (node (ref "D6") (pin "1") (pinfunction "1_1") (pintype "passive"))
      (node (ref "D8") (pin "1") (pinfunction "1_1") (pintype "passive"))
      (node (ref "D9") (pin "1") (pinfunction "1_1") (pintype "passive"))
      (node (ref "EPD_C1") (pin "1") (pinfunction "1_1") (pintype "passive"))
      (node (ref "EPD_C10") (pin "1") (pinfunction "1_1") (pintype "passive"))
      (node (ref "EPD_C11") (pin "1") (pinfunction "1_1") (pintype "passive"))
      (node (ref "EPD_C12") (pin "1") (pinfunction "1_1") (pintype "passive"))
      (node (ref "EPD_C2") (pin "1") (pinfunction "1_1") (pintype "passive"))
      (node (ref "EPD_C5") (pin "1") (pinfunction "1_1") (pintype "passive"))
      (node (ref "EPD_C6") (pin "1") (pinfunction "1_1") (pintype "passive"))
      (node (ref "EPD_C7") (pin "1") (pinfunction "1_1") (pintype "passive"))
      (node (ref "EPD_C8") (pin "1") (pinfunction "1_1") (pintype "passive"))
      (node (ref "EPD_C9") (pin "1") (pinfunction "1_1") (pintype "passive"))
      (node (ref "IC1") (pin "3") (pinfunction "GND_3") (pintype "bidirectional"))
      (node (ref "IC4") (pin "2") (pinfunction "VSS_2") (pintype "bidirectional"))
      (node (ref "J1") (pin "A1") (pinfunction "A1_A1") (pintype "bidirectional"))
      (node (ref "J1") (pin "A12") (pinfunction "A12_A12") (pintype "bidirectional"))
      (node (ref "J1") (pin "B1") (pinfunction "B1_B1") (pintype "bidirectional"))
      (node (ref "J1") (pin "B12") (pinfunction "B12_B12") (pintype "bidirectional"))
      (node (ref "J1") (pin "MP1") (pinfunction "MP1_MP1") (pintype "bidirectional"))
      (node (ref "J1") (pin "MP2") (pinfunction "MP2_MP2") (pintype "bidirectional"))
      (node (ref "J1") (pin "MP3") (pinfunction "MP3_MP3") (pintype "bidirectional"))
      (node (ref "J1") (pin "MP4") (pinfunction "MP4_MP4") (pintype "bidirectional"))
      (node (ref "J2") (pin "17") (pinfunction "17_17") (pintype "bidirectional"))
      (node (ref "J2") (pin "8") (pinfunction "8_8") (pintype "bidirectional"))
      (node (ref "J2") (pin "MP1") (pinfunction "MP1_MP1") (pintype "bidirectional"))
      (node (ref "J2") (pin "MP2") (pinfunction "MP2_MP2") (pintype "bidirectional"))
      (node (ref "J3") (pin "1") (pinfunction "1_1") (pintype "power_in"))
      (node (ref "J4") (pin "G1") (pinfunction "GND_1_G1") (pintype "bidirectional"))
      (node (ref "J4") (pin "G2") (pinfunction "GND_2_G2") (pintype "bidirectional"))
      (node (ref "J4") (pin "G3") (pinfunction "GND_3_G3") (pintype "bidirectional"))
      (node (ref "J4") (pin "G4") (pinfunction "GND_4_G4") (pintype "bidirectional"))
      (node (ref "J4") (pin "P6") (pinfunction "VSS_P6") (pintype "bidirectional"))
      (node (ref "MCP73831") (pin "2") (pinfunction "VSS_2") (pintype "power_in"))
      (node (ref "R1_PWRUSB") (pin "1") (pinfunction "1_1") (pintype "passive"))
      (node (ref "R2") (pin "1") (pinfunction "1_1") (pintype "passive"))
      (node (ref "R2-USB") (pin "2") (pinfunction "2_2") (pintype "passive"))
      (node (ref "R2-USB1") (pin "1") (pinfunction "1_1") (pintype "passive"))
      (node (ref "R2_BAT") (pin "1") (pinfunction "1_1") (pintype "passive"))
      (node (ref "R4") (pin "1") (pinfunction "1_1") (pintype "passive"))
      (node (ref "RESET_BUTTON") (pin "1") (pinfunction "1_1") (pintype "passive"))
      (node (ref "RESET_BUTTON") (pin "2") (pinfunction "2_2") (pintype "passive"))
      (node (ref "SENSOR2") (pin "1") (pinfunction "GND_1") (pintype "power_in"))
      (node (ref "SENSOR2") (pin "5") (pinfunction "SDO_5") (pintype "bidirectional"))
      (node (ref "SENSOR2") (pin "7") (pinfunction "GND_7") (pintype "power_in"))
      (node (ref "SJ1") (pin "1") (pinfunction "1_1") (pintype "passive"))
      (node (ref "TP4") (pin "TP") (pinfunction "TP_TP") (pintype "input"))
      (node (ref "TP5") (pin "TP") (pinfunction "TP_TP") (pintype "input"))
      (node (ref "U1") (pin "4") (pinfunction "GND_4") (pintype "power_in"))
      (node (ref "U1") (pin "9") (pinfunction "EXP_9") (pintype "passive"))
      (node (ref "U2") (pin "1") (pinfunction "GND_1") (pintype "power_in"))
      (node (ref "U2") (pin "28") (pinfunction "GND_28") (pintype "power_in"))
      (node (ref "U2") (pin "29_1") (pinfunction "GND_29_1") (pintype "power_in"))
      (node (ref "U2") (pin "29_2") (pinfunction "GND_29_2") (pintype "power_in"))
      (node (ref "U2") (pin "29_3") (pinfunction "GND_29_3") (pintype "power_in"))
      (node (ref "U2") (pin "29_4") (pinfunction "GND_29_4") (pintype "power_in"))
      (node (ref "U2") (pin "29_5") (pinfunction "GND_29_5") (pintype "power_in"))
      (node (ref "U2") (pin "29_6") (pinfunction "GND_29_6") (pintype "power_in"))
      (node (ref "U2") (pin "29_7") (pinfunction "GND_29_7") (pintype "power_in"))
      (node (ref "U2") (pin "29_8") (pinfunction "GND_29_8") (pintype "power_in"))
      (node (ref "U2") (pin "29_9") (pinfunction "GND_29_9") (pintype "power_in"))
      (node (ref "U3") (pin "13") (pinfunction "GND_13") (pintype "power_in"))
      (node (ref "U4") (pin "1") (pinfunction "CTG_1") (pintype "power_in"))
      (node (ref "U4") (pin "4") (pinfunction "GND_4") (pintype "power_in"))
      (node (ref "U4") (pin "6") (pinfunction "QSTRT_6") (pintype "input"))
      (node (ref "U4") (pin "9") (pinfunction "EP_9") (pintype "power_in"))
    )
    (net (code "14") (name "GPIO8") (class "Default")
      (node (ref "R1") (pin "1") (pinfunction "1_1") (pintype "passive"))
      (node (ref "U2") (pin "10") (pinfunction "IO8_10") (pintype "bidirectional"))
    )
    (net (code "15") (name "I2C_PW") (class "Default")
      (node (ref "C1") (pin "1") (pinfunction "1_1") (pintype "passive"))
      (node (ref "C2") (pin "1") (pinfunction "1_1") (pintype "passive"))
      (node (ref "R1_PINH") (pin "2") (pinfunction "2_2") (pintype "passive"))
      (node (ref "R2-PINH") (pin "2") (pinfunction "2_2") (pintype "passive"))
      (node (ref "SENSOR2") (pin "2") (pinfunction "CSB_2") (pintype "input"))
      (node (ref "SENSOR2") (pin "6") (pinfunction "VDDIO_6") (pintype "power_in"))
      (node (ref "SENSOR2") (pin "8") (pinfunction "VDD_8") (pintype "power_in"))
      (node (ref "U2") (pin "17") (pinfunction "IO19_17") (pintype "bidirectional"))
    )
    (net (code "16") (name "INT_RTC") (class "Default")
      (node (ref "R1_PINH1") (pin "1") (pinfunction "1_1") (pintype "passive"))
      (node (ref "TP15") (pin "TP") (pinfunction "TP_TP") (pintype "input"))
      (node (ref "U2") (pin "8") (pinfunction "IO0_8") (pintype "bidirectional"))
      (node (ref "U3") (pin "3") (pinfunction "SQW/~{INT}_3") (pintype "output"))
    )
    (net (code "17") (name "IO{slash}BOOT") (class "Default")
      (node (ref "BOOT_BUTTON") (pin "3") (pinfunction "3_3") (pintype "passive"))
      (node (ref "BOOT_BUTTON") (pin "4") (pinfunction "4_4") (pintype "passive"))
      (node (ref "C6") (pin "1") (pinfunction "1_1") (pintype "passive"))
      (node (ref "R_BOOT") (pin "1") (pinfunction "1_1") (pintype "passive"))
      (node (ref "U2") (pin "15") (pinfunction "IO9_15") (pintype "bidirectional"))
    )
    (net (code "18") (name "IO{slash}CHANGE") (class "Default")
      (node (ref "C10") (pin "1") (pinfunction "1_1") (pintype "passive"))
      (node (ref "CHANGE_BUTTON") (pin "3") (pinfunction "3_3") (pintype "passive"))
      (node (ref "CHANGE_BUTTON") (pin "4") (pinfunction "4_4") (pintype "passive"))
      (node (ref "R_CHANGE") (pin "1") (pinfunction "1_1") (pintype "passive"))
      (node (ref "U2") (pin "23") (pinfunction "IO15_23") (pintype "bidirectional"))
    )
    (net (code "19") (name "MISO") (class "Default")
      (node (ref "D12") (pin "2") (pinfunction "2_2") (pintype "passive"))
      (node (ref "J4") (pin "P7") (pinfunction "DAT0_P7") (pintype "bidirectional"))
      (node (ref "R8") (pin "1") (pinfunction "1_1") (pintype "passive"))
      (node (ref "TP6") (pin "TP") (pinfunction "TP_TP") (pintype "input"))
      (node (ref "U1") (pin "2") (pinfunction "DO(IO1)_2") (pintype "bidirectional"))
      (node (ref "U2") (pin "27") (pinfunction "IO2_27") (pintype "bidirectional"))
    )
    (net (code "20") (name "MOSI") (class "Default")
      (node (ref "D11") (pin "2") (pinfunction "2_2") (pintype "passive"))
      (node (ref "J2") (pin "14") (pinfunction "14_14") (pintype "bidirectional"))
      (node (ref "J4") (pin "P3") (pinfunction "CMD_P3") (pintype "bidirectional"))
      (node (ref "R7") (pin "1") (pinfunction "1_1") (pintype "passive"))
      (node (ref "TP7") (pin "TP") (pinfunction "TP_TP") (pintype "input"))
      (node (ref "U1") (pin "5") (pinfunction "DI(IO0)_5") (pintype "bidirectional"))
      (node (ref "U2") (pin "7") (pinfunction "IO7_7") (pintype "bidirectional"))
    )
    (net (code "21") (name "Net-(CHG_LED-PadC)") (class "Default")
      (node (ref "CHG_LED") (pin "C") (pinfunction "C_C") (pintype "passive"))
      (node (ref "R1_BAT") (pin "1") (pinfunction "1_1") (pintype "passive"))
    )
    (net (code "22") (name "Net-(D2-CATHODE)") (class "Default")
      (node (ref "C1_BAT1") (pin "1") (pinfunction "1_1") (pintype "passive"))
      (node (ref "D2") (pin "1") (pinfunction "CATHODE_1") (pintype "bidirectional"))
      (node (ref "IC4") (pin "1") (pinfunction "VIN_1") (pintype "bidirectional"))
      (node (ref "IC4") (pin "3") (pinfunction "CE_3") (pintype "bidirectional"))
      (node (ref "Q1") (pin "2") (pinfunction "S_2") (pintype "bidirectional"))
    )
    (net (code "23") (name "Net-(D3-A)") (class "Default")
      (node (ref "C4") (pin "1") (pinfunction "1_1") (pintype "passive"))
      (node (ref "D3") (pin "2") (pinfunction "A_2") (pintype "bidirectional"))
      (node (ref "D4") (pin "1") (pinfunction "K_1") (pintype "bidirectional"))
    )
    (net (code "24") (name "Net-(D7-CATHODE)") (class "Default")
      (node (ref "D7") (pin "1") (pinfunction "CATHODE_1") (pintype "bidirectional"))
      (node (ref "R_CAPACITOR") (pin "1") (pinfunction "1_1") (pintype "passive"))
    )
    (net (code "25") (name "Net-(EPD_C1-Pad2)") (class "Default")
      (node (ref "EPD_C1") (pin "2") (pinfunction "2_2") (pintype "passive"))
      (node (ref "J2") (pin "4") (pinfunction "4_4") (pintype "bidirectional"))
    )
    (net (code "26") (name "Net-(EPD_C2-Pad2)") (class "Default")
      (node (ref "EPD_C2") (pin "2") (pinfunction "2_2") (pintype "passive"))
      (node (ref "J2") (pin "5") (pinfunction "5_5") (pintype "bidirectional"))
    )
    (net (code "27") (name "Net-(EPD_C6-Pad2)") (class "Default")
      (node (ref "EPD_C6") (pin "2") (pinfunction "2_2") (pintype "passive"))
      (node (ref "J2") (pin "18") (pinfunction "18_18") (pintype "bidirectional"))
    )
    (net (code "28") (name "Net-(EPD_C7-Pad2)") (class "Default")
      (node (ref "EPD_C7") (pin "2") (pinfunction "2_2") (pintype "passive"))
      (node (ref "J2") (pin "19") (pinfunction "19_19") (pintype "bidirectional"))
    )
    (net (code "29") (name "Net-(EPD_C8-Pad2)") (class "Default")
      (node (ref "EPD_C8") (pin "2") (pinfunction "2_2") (pintype "passive"))
      (node (ref "J2") (pin "20") (pinfunction "20_20") (pintype "bidirectional"))
    )
    (net (code "30") (name "Net-(EPD_C10-Pad2)") (class "Default")
      (node (ref "EPD_C10") (pin "2") (pinfunction "2_2") (pintype "passive"))
      (node (ref "J2") (pin "22") (pinfunction "22_22") (pintype "bidirectional"))
    )
    (net (code "31") (name "Net-(EPD_C12-Pad2)") (class "Default")
      (node (ref "EPD_C12") (pin "2") (pinfunction "2_2") (pintype "passive"))
      (node (ref "J2") (pin "24") (pinfunction "24_24") (pintype "bidirectional"))
    )
    (net (code "32") (name "Net-(IC1-CT)") (class "Default")
      (node (ref "C_DELAY") (pin "1") (pinfunction "1_1") (pintype "passive"))
      (node (ref "IC1") (pin "5") (pinfunction "CT_5") (pintype "bidirectional"))
    )
    (net (code "33") (name "Net-(J1-PadA5)") (class "Default")
      (node (ref "J1") (pin "A5") (pinfunction "A5_A5") (pintype "bidirectional"))
      (node (ref "R2-USB1") (pin "2") (pinfunction "2_2") (pintype "passive"))
    )
    (net (code "34") (name "Net-(J1-PadB5)") (class "Default")
      (node (ref "J1") (pin "B5") (pinfunction "B5_B5") (pintype "bidirectional"))
      (node (ref "R2-USB") (pin "1") (pinfunction "1_1") (pintype "passive"))
    )
    (net (code "35") (name "Net-(MCP73831-PROG)") (class "Default")
      (node (ref "MCP73831") (pin "5") (pinfunction "PROG_5") (pintype "input"))
      (node (ref "R2_BAT") (pin "2") (pinfunction "2_2") (pintype "passive"))
    )
    (net (code "36") (name "Net-(MCP73831-STAT)") (class "Default")
      (node (ref "MCP73831") (pin "1") (pinfunction "STAT_1") (pintype "output"))
      (node (ref "R1_BAT") (pin "2") (pinfunction "2_2") (pintype "passive"))
    )
    (net (code "37") (name "PREVGH") (class "Default")
      (node (ref "D5") (pin "1") (pinfunction "K_1") (pintype "bidirectional"))
      (node (ref "EPD_C9") (pin "2") (pinfunction "2_2") (pintype "passive"))
      (node (ref "J2") (pin "21") (pinfunction "21_21") (pintype "bidirectional"))
    )
    (net (code "38") (name "PREVGL") (class "Default")
      (node (ref "D4") (pin "2") (pinfunction "A_2") (pintype "bidirectional"))
      (node (ref "EPD_C11") (pin "2") (pinfunction "2_2") (pintype "passive"))
      (node (ref "J2") (pin "23") (pinfunction "23_23") (pintype "bidirectional"))
    )
    (net (code "39") (name "RESE") (class "Default")
      (node (ref "J2") (pin "3") (pinfunction "3_3") (pintype "bidirectional"))
      (node (ref "Q3") (pin "2") (pinfunction "S_2") (pintype "bidirectional"))
      (node (ref "R3") (pin "2") (pinfunction "2_2") (pintype "passive"))
    )
    (net (code "40") (name "RESE'") (class "Default")
      (node (ref "R2") (pin "2") (pinfunction "2_2") (pintype "passive"))
      (node (ref "R3") (pin "1") (pinfunction "1_1") (pintype "passive"))
      (node (ref "SJ1") (pin "2") (pinfunction "2_2") (pintype "passive"))
    )
    (net (code "41") (name "RESET") (class "Default")
      (node (ref "C5") (pin "1") (pinfunction "1_1") (pintype "passive"))
      (node (ref "IC1") (pin "1") (pinfunction "VOUT_1") (pintype "bidirectional"))
      (node (ref "RESET_BUTTON") (pin "3") (pinfunction "3_3") (pintype "passive"))
      (node (ref "RESET_BUTTON") (pin "4") (pinfunction "4_4") (pintype "passive"))
      (node (ref "R_RESET") (pin "1") (pinfunction "1_1") (pintype "passive"))
      (node (ref "U2") (pin "3") (pinfunction "EN_3") (pintype "input"))
    )
    (net (code "42") (name "RTC_RST") (class "Default")
      (node (ref "U2") (pin "16") (pinfunction "IO18_16") (pintype "bidirectional"))
      (node (ref "U3") (pin "4") (pinfunction "~{RST}_4") (pintype "input"))
    )
    (net (code "43") (name "RX") (class "Default")
      (node (ref "TP2") (pin "TP") (pinfunction "TP_TP") (pintype "input"))
      (node (ref "U2") (pin "24") (pinfunction "RXD0/GPIO17_24") (pintype "bidirectional"))
    )
    (net (code "44") (name "SCK") (class "Default")
      (node (ref "D10") (pin "2") (pinfunction "2_2") (pintype "passive"))
      (node (ref "J2") (pin "13") (pinfunction "13_13") (pintype "bidirectional"))
      (node (ref "J4") (pin "P5") (pinfunction "CLK_P5") (pintype "bidirectional"))
      (node (ref "R6") (pin "1") (pinfunction "1_1") (pintype "passive"))
      (node (ref "TP8") (pin "TP") (pinfunction "TP_TP") (pintype "input"))
      (node (ref "U1") (pin "6") (pinfunction "CLK_6") (pintype "input"))
      (node (ref "U2") (pin "6") (pinfunction "IO6_6") (pintype "bidirectional"))
    )
    (net (code "45") (name "SCL") (class "Default")
      (node (ref "J3") (pin "4") (pinfunction "4_4") (pintype "passive"))
      (node (ref "R2-PINH") (pin "1") (pinfunction "1_1") (pintype "passive"))
      (node (ref "SENSOR2") (pin "4") (pinfunction "SCK_4") (pintype "input"))
      (node (ref "U2") (pin "20") (pinfunction "IO22_20") (pintype "bidirectional"))
      (node (ref "U3") (pin "16") (pinfunction "SCL_16") (pintype "input"))
      (node (ref "U4") (pin "7") (pinfunction "SCL_7") (pintype "input"))
    )
    (net (code "46") (name "SDA") (class "Default")
      (node (ref "J3") (pin "3") (pinfunction "3_3") (pintype "passive"))
      (node (ref "R1_PINH") (pin "1") (pinfunction "1_1") (pintype "passive"))
      (node (ref "SENSOR2") (pin "3") (pinfunction "SDI_3") (pintype "bidirectional"))
      (node (ref "U2") (pin "19") (pinfunction "IO21_19") (pintype "bidirectional"))
      (node (ref "U3") (pin "15") (pinfunction "SDA_15") (pintype "bidirectional"))
      (node (ref "U4") (pin "8") (pinfunction "SDA_8") (pintype "bidirectional"))
    )
    (net (code "47") (name "SRC") (class "Default")
      (node (ref "C4") (pin "2") (pinfunction "2_2") (pintype "passive"))
      (node (ref "D5") (pin "2") (pinfunction "A_2") (pintype "bidirectional"))
      (node (ref "L1") (pin "1") (pinfunction "1_1") (pintype "passive"))
      (node (ref "Q3") (pin "3") (pinfunction "D_3") (pintype "bidirectional"))
    )
    (net (code "48") (name "SS_SD") (class "Default")
      (node (ref "D8") (pin "2") (pinfunction "2_2") (pintype "passive"))
      (node (ref "J4") (pin "P2") (pinfunction "CD/DAT3_P2") (pintype "bidirectional"))
      (node (ref "R10") (pin "1") (pinfunction "1_1") (pintype "passive"))
      (node (ref "U2") (pin "4") (pinfunction "IO4_4") (pintype "bidirectional"))
    )
    (net (code "49") (name "TX") (class "Default")
      (node (ref "TP1") (pin "TP") (pinfunction "TP_TP") (pintype "input"))
      (node (ref "U2") (pin "25") (pinfunction "TXD0/GPIO16_25") (pintype "bidirectional"))
    )
    (net (code "50") (name "USB_D+") (class "Default")
      (node (ref "D1") (pin "1") (pinfunction "I/O1_1_1") (pintype "bidirectional"))
      (node (ref "U2") (pin "14") (pinfunction "IO13_14") (pintype "bidirectional"))
    )
    (net (code "51") (name "USB_D-") (class "Default")
      (node (ref "D1") (pin "3") (pinfunction "I/O2_1_3") (pintype "bidirectional"))
      (node (ref "U2") (pin "13") (pinfunction "IO12_13") (pintype "bidirectional"))
    )
    (net (code "52") (name "VBAT") (class "Default")
      (node (ref "C2_BAT") (pin "1") (pinfunction "1_1") (pintype "passive"))
      (node (ref "MCP73831") (pin "3") (pinfunction "VBAT_3") (pintype "power_in"))
      (node (ref "Q1") (pin "3") (pinfunction "D_3") (pintype "bidirectional"))
      (node (ref "TP3") (pin "TP") (pinfunction "TP_TP") (pintype "input"))
      (node (ref "U4") (pin "2") (pinfunction "CELL_2") (pintype "power_in"))
      (node (ref "U4") (pin "3") (pinfunction "VDD_3") (pintype "power_in"))
    )
    (net (code "53") (name "VBUS") (class "Default")
      (node (ref "C1_BAT") (pin "1") (pinfunction "1_1") (pintype "passive"))
      (node (ref "C4_USB") (pin "1") (pinfunction "1_1") (pintype "passive"))
      (node (ref "C5_USB") (pin "1") (pinfunction "1_1") (pintype "passive"))
      (node (ref "CHG_LED") (pin "A") (pinfunction "A_A") (pintype "passive"))
      (node (ref "D1") (pin "5") (pinfunction "VBUS_5") (pintype "bidirectional"))
      (node (ref "D2") (pin "2") (pinfunction "ANODE_2") (pintype "bidirectional"))
      (node (ref "MCP73831") (pin "4") (pinfunction "VIN_4") (pintype "power_in"))
      (node (ref "PFMF.050.1") (pin "2") (pinfunction "2_2") (pintype "passive"))
      (node (ref "Q1") (pin "1") (pinfunction "G_1") (pintype "bidirectional"))
      (node (ref "R1_PWRUSB") (pin "2") (pinfunction "2_2") (pintype "passive"))
      (node (ref "TP14") (pin "TP") (pinfunction "TP_TP") (pintype "input"))
    )
    (net (code "54") (name "VRTC") (class "Default")
      (node (ref "C10_SUPERCAP") (pin "2") (pinfunction "2_2") (pintype "passive"))
      (node (ref "C8") (pin "1") (pinfunction "1_1") (pintype "passive"))
      (node (ref "R_CAPACITOR") (pin "2") (pinfunction "2_2") (pintype "passive"))
      (node (ref "U3") (pin "14") (pinfunction "VBAT_14") (pintype "power_in"))
    )
    (net (code "55") (name "VUSB") (class "Default")
      (node (ref "J1") (pin "A4") (pinfunction "A4_A4") (pintype "bidirectional"))
      (node (ref "J1") (pin "A9") (pinfunction "A9_A9") (pintype "bidirectional"))
      (node (ref "J1") (pin "B4") (pinfunction "B4_B4") (pintype "bidirectional"))
      (node (ref "J1") (pin "B9") (pinfunction "B9_B9") (pintype "bidirectional"))
      (node (ref "PFMF.050.1") (pin "1") (pinfunction "1_1") (pintype "passive"))
    )
    (net (code "56") (name "unconnected-(IC1-NC-Pad4)") (class "Default")
      (node (ref "IC1") (pin "4") (pinfunction "NC_4") (pintype "no_connect"))
    )
    (net (code "57") (name "unconnected-(IC4-NC-Pad4)") (class "Default")
      (node (ref "IC4") (pin "4") (pinfunction "NC_4") (pintype "no_connect"))
    )
    (net (code "58") (name "unconnected-(J1-PadA8)") (class "Default")
      (node (ref "J1") (pin "A8") (pinfunction "A8_A8") (pintype "bidirectional"))
    )
    (net (code "59") (name "unconnected-(J1-PadB8)") (class "Default")
      (node (ref "J1") (pin "B8") (pinfunction "B8_B8") (pintype "bidirectional"))
    )
    (net (code "60") (name "unconnected-(J2-Pad1)") (class "Default")
      (node (ref "J2") (pin "1") (pinfunction "1_1") (pintype "bidirectional"))
    )
    (net (code "61") (name "unconnected-(J2-Pad6)") (class "Default")
      (node (ref "J2") (pin "6") (pinfunction "6_6") (pintype "bidirectional"))
    )
    (net (code "62") (name "unconnected-(J2-Pad7)") (class "Default")
      (node (ref "J2") (pin "7") (pinfunction "7_7") (pintype "bidirectional"))
    )
    (net (code "63") (name "unconnected-(J4-DAT1-PadP8)") (class "Default")
      (node (ref "J4") (pin "P8") (pinfunction "DAT1_P8") (pintype "bidirectional"))
    )
    (net (code "64") (name "unconnected-(J4-DAT2-PadP1)") (class "Default")
      (node (ref "J4") (pin "P1") (pinfunction "DAT2_P1") (pintype "bidirectional"))
    )
    (net (code "65") (name "unconnected-(J4-DETECTION_1-PadS1)") (class "Default")
      (node (ref "J4") (pin "S1") (pinfunction "DETECTION_1_S1") (pintype "bidirectional"))
    )
    (net (code "66") (name "unconnected-(J4-DETECTION_2-PadS2)") (class "Default")
      (node (ref "J4") (pin "S2") (pinfunction "DETECTION_2_S2") (pintype "bidirectional"))
    )
    (net (code "67") (name "unconnected-(U2-NC-Pad22)") (class "Default")
      (node (ref "U2") (pin "22") (pinfunction "NC_22") (pintype "no_connect"))
    )
    (net (code "68") (name "unconnected-(U4-~{ALERT}-Pad5)") (class "Default")
      (node (ref "U4") (pin "5") (pinfunction "~{ALERT}_5") (pintype "output"))
    )
  )
)
